# mm.net
KiCad netlist of a schematic drawn in EAGLE
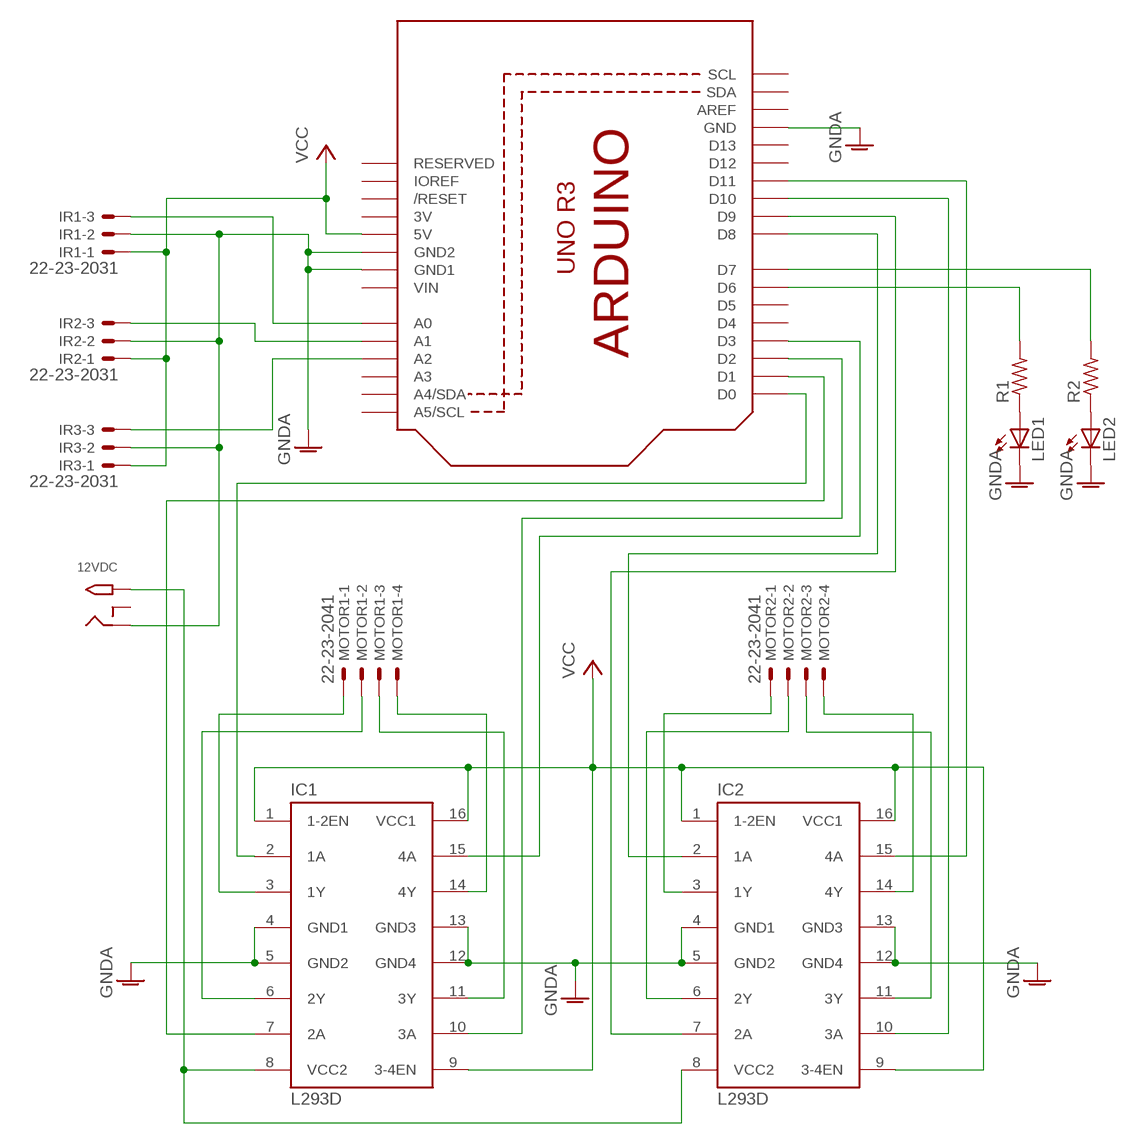
[diagram p0: schematic, sheet 1]

(export (version "E")
  (design (tool "Eeschema 10.0.6"))
  (components
    (comp (ref "12VDC")
      (value "2.1MMJACKTHM")
      (footprint "eagle-import:PJ-102A")
      (libsource (lib "eagle-import") (part "2.1MMJACKTHM"))
    )
    (comp (ref "IC1")
      (value "L293D")
      (footprint "eagle-import:DIL16")
      (libsource (lib "eagle-import") (part "L293D"))
    )
    (comp (ref "IC2")
      (value "L293D")
      (footprint "eagle-import:DIL16")
      (libsource (lib "eagle-import") (part "L293D"))
    )
    (comp (ref "IR1")
      (value "22-23-2031")
      (footprint "eagle-import:22-23-2031")
      (fields (field (name "MF") "MOLEX"))
      (libsource (lib "eagle-import") (part "22-23-2031"))
    )
    (comp (ref "IR2")
      (value "22-23-2031")
      (footprint "eagle-import:22-23-2031")
      (fields (field (name "MF") "MOLEX"))
      (libsource (lib "eagle-import") (part "22-23-2031"))
    )
    (comp (ref "IR3")
      (value "22-23-2031")
      (footprint "eagle-import:22-23-2031")
      (fields (field (name "MF") "MOLEX"))
      (libsource (lib "eagle-import") (part "22-23-2031"))
    )
    (comp (ref "LED1")
      (value "LED3MM")
      (footprint "eagle-import:LED3MM")
      (libsource (lib "eagle-import") (part "LED3MM"))
    )
    (comp (ref "LED2")
      (value "LED3MM")
      (footprint "eagle-import:LED3MM")
      (libsource (lib "eagle-import") (part "LED3MM"))
    )
    (comp (ref "MOTOR1")
      (value "22-23-2041")
      (footprint "eagle-import:22-23-2041")
      (fields (field (name "MF") "MOLEX"))
      (libsource (lib "eagle-import") (part "22-23-2041"))
    )
    (comp (ref "MOTOR2")
      (value "22-23-2041")
      (footprint "eagle-import:22-23-2041")
      (fields (field (name "MF") "MOLEX"))
      (libsource (lib "eagle-import") (part "22-23-2041"))
    )
    (comp (ref "R1")
      (value "R-US_0204/5")
      (footprint "eagle-import:0204_5")
      (libsource (lib "eagle-import") (part "R-US_0204/5"))
    )
    (comp (ref "R2")
      (value "R-US_0204/5")
      (footprint "eagle-import:0204_5")
      (libsource (lib "eagle-import") (part "R-US_0204/5"))
    )
    (comp (ref "U1")
      (value "ARDUINOR3-DIMENSION")
      (footprint "eagle-import:ARDUINOR3")
      (libsource (lib "eagle-import") (part "ARDUINOR3-DIMENSION"))
    )
  )
  (nets
    (net (code "1") (name "/3V") (class "Default")
      (node (ref "U1") (pin "3V") (pinfunction "3V_3V") (pintype "power_in"))
    )
    (net (code "2") (name "/VIN") (class "Default")
      (node (ref "U1") (pin "VIN") (pinfunction "VIN_VIN") (pintype "power_in"))
    )
    (net (code "3") (name "GNDA") (class "Default")
      (node (ref "12VDC") (pin "RING") (pinfunction "RING_RING") (pintype "bidirectional"))
      (node (ref "IC1") (pin "12") (pinfunction "GND4_12") (pintype "power_in"))
      (node (ref "IC1") (pin "13") (pinfunction "GND3_13") (pintype "power_in"))
      (node (ref "IC1") (pin "4") (pinfunction "GND1_4") (pintype "power_in"))
      (node (ref "IC1") (pin "5") (pinfunction "GND2_5") (pintype "power_in"))
      (node (ref "IC2") (pin "12") (pinfunction "GND4_12") (pintype "power_in"))
      (node (ref "IC2") (pin "13") (pinfunction "GND3_13") (pintype "power_in"))
      (node (ref "IC2") (pin "4") (pinfunction "GND1_4") (pintype "power_in"))
      (node (ref "IC2") (pin "5") (pinfunction "GND2_5") (pintype "power_in"))
      (node (ref "IR1") (pin "2") (pinfunction "S_2") (pintype "passive"))
      (node (ref "IR2") (pin "2") (pinfunction "S_2") (pintype "passive"))
      (node (ref "IR3") (pin "2") (pinfunction "S_2") (pintype "passive"))
      (node (ref "LED1") (pin "K") (pinfunction "C_K") (pintype "passive"))
      (node (ref "LED2") (pin "K") (pinfunction "C_K") (pintype "passive"))
      (node (ref "U1") (pin "GND") (pinfunction "GND_GND") (pintype "power_in"))
      (node (ref "U1") (pin "GND1") (pinfunction "GND1_GND1") (pintype "power_in"))
      (node (ref "U1") (pin "GND2") (pinfunction "GND2_GND2") (pintype "power_in"))
    )
    (net (code "4") (name "Net-(IC1-1A)") (class "Default")
      (node (ref "IC1") (pin "2") (pinfunction "1A_2") (pintype "input"))
      (node (ref "U1") (pin "D0") (pinfunction "D0_D0") (pintype "bidirectional"))
    )
    (net (code "5") (name "Net-(IC1-1Y)") (class "Default")
      (node (ref "IC1") (pin "3") (pinfunction "1Y_3") (pintype "output"))
      (node (ref "MOTOR1") (pin "1") (pinfunction "S_1") (pintype "passive"))
    )
    (net (code "6") (name "Net-(IC1-2A)") (class "Default")
      (node (ref "IC1") (pin "7") (pinfunction "2A_7") (pintype "input"))
      (node (ref "U1") (pin "D1") (pinfunction "D1_D1") (pintype "bidirectional"))
    )
    (net (code "7") (name "Net-(IC1-2Y)") (class "Default")
      (node (ref "IC1") (pin "6") (pinfunction "2Y_6") (pintype "output"))
      (node (ref "MOTOR1") (pin "2") (pinfunction "S_2") (pintype "passive"))
    )
    (net (code "8") (name "Net-(IC1-3A)") (class "Default")
      (node (ref "IC1") (pin "10") (pinfunction "3A_10") (pintype "input"))
      (node (ref "U1") (pin "D2") (pinfunction "D2_D2") (pintype "bidirectional"))
    )
    (net (code "9") (name "Net-(IC1-3Y)") (class "Default")
      (node (ref "IC1") (pin "11") (pinfunction "3Y_11") (pintype "output"))
      (node (ref "MOTOR1") (pin "3") (pinfunction "S_3") (pintype "passive"))
    )
    (net (code "10") (name "Net-(IC1-4A)") (class "Default")
      (node (ref "IC1") (pin "15") (pinfunction "4A_15") (pintype "input"))
      (node (ref "U1") (pin "D3") (pinfunction "D3_D3") (pintype "bidirectional"))
    )
    (net (code "11") (name "Net-(IC1-4Y)") (class "Default")
      (node (ref "IC1") (pin "14") (pinfunction "4Y_14") (pintype "output"))
      (node (ref "MOTOR1") (pin "4") (pinfunction "S_4") (pintype "passive"))
    )
    (net (code "12") (name "Net-(IC1-VCC2)") (class "Default")
      (node (ref "12VDC") (pin "TIP") (pinfunction "TIP_TIP") (pintype "bidirectional"))
      (node (ref "IC1") (pin "8") (pinfunction "VCC2_8") (pintype "power_in"))
      (node (ref "IC2") (pin "8") (pinfunction "VCC2_8") (pintype "power_in"))
    )
    (net (code "13") (name "Net-(IC2-1A)") (class "Default")
      (node (ref "IC2") (pin "2") (pinfunction "1A_2") (pintype "input"))
      (node (ref "U1") (pin "D8") (pinfunction "D8_D8") (pintype "bidirectional"))
    )
    (net (code "14") (name "Net-(IC2-1Y)") (class "Default")
      (node (ref "IC2") (pin "3") (pinfunction "1Y_3") (pintype "output"))
      (node (ref "MOTOR2") (pin "1") (pinfunction "S_1") (pintype "passive"))
    )
    (net (code "15") (name "Net-(IC2-2A)") (class "Default")
      (node (ref "IC2") (pin "7") (pinfunction "2A_7") (pintype "input"))
      (node (ref "U1") (pin "D9") (pinfunction "D9_D9") (pintype "bidirectional"))
    )
    (net (code "16") (name "Net-(IC2-2Y)") (class "Default")
      (node (ref "IC2") (pin "6") (pinfunction "2Y_6") (pintype "output"))
      (node (ref "MOTOR2") (pin "2") (pinfunction "S_2") (pintype "passive"))
    )
    (net (code "17") (name "Net-(IC2-3A)") (class "Default")
      (node (ref "IC2") (pin "10") (pinfunction "3A_10") (pintype "input"))
      (node (ref "U1") (pin "D10") (pinfunction "D10_D10") (pintype "bidirectional"))
    )
    (net (code "18") (name "Net-(IC2-3Y)") (class "Default")
      (node (ref "IC2") (pin "11") (pinfunction "3Y_11") (pintype "output"))
      (node (ref "MOTOR2") (pin "3") (pinfunction "S_3") (pintype "passive"))
    )
    (net (code "19") (name "Net-(IC2-4A)") (class "Default")
      (node (ref "IC2") (pin "15") (pinfunction "4A_15") (pintype "input"))
      (node (ref "U1") (pin "D11") (pinfunction "D11_D11") (pintype "bidirectional"))
    )
    (net (code "20") (name "Net-(IC2-4Y)") (class "Default")
      (node (ref "IC2") (pin "14") (pinfunction "4Y_14") (pintype "output"))
      (node (ref "MOTOR2") (pin "4") (pinfunction "S_4") (pintype "passive"))
    )
    (net (code "21") (name "Net-(IR1C-S)") (class "Default")
      (node (ref "IR1") (pin "3") (pinfunction "S_3") (pintype "passive"))
      (node (ref "U1") (pin "A0") (pinfunction "A0_A0") (pintype "bidirectional"))
    )
    (net (code "22") (name "Net-(IR2C-S)") (class "Default")
      (node (ref "IR2") (pin "3") (pinfunction "S_3") (pintype "passive"))
      (node (ref "U1") (pin "A1") (pinfunction "A1_A1") (pintype "bidirectional"))
    )
    (net (code "23") (name "Net-(IR3C-S)") (class "Default")
      (node (ref "IR3") (pin "3") (pinfunction "S_3") (pintype "passive"))
      (node (ref "U1") (pin "A2") (pinfunction "A2_A2") (pintype "bidirectional"))
    )
    (net (code "24") (name "Net-(LED1-PadA)") (class "Default")
      (node (ref "LED1") (pin "A") (pinfunction "A_A") (pintype "passive"))
      (node (ref "R1") (pin "1") (pinfunction "1_1") (pintype "passive"))
    )
    (net (code "25") (name "Net-(LED2-PadA)") (class "Default")
      (node (ref "LED2") (pin "A") (pinfunction "A_A") (pintype "passive"))
      (node (ref "R2") (pin "1") (pinfunction "1_1") (pintype "passive"))
    )
    (net (code "26") (name "Net-(R1-Pad2)") (class "Default")
      (node (ref "R1") (pin "2") (pinfunction "2_2") (pintype "passive"))
      (node (ref "U1") (pin "D6") (pinfunction "D6_D6") (pintype "bidirectional"))
    )
    (net (code "27") (name "Net-(R2-Pad2)") (class "Default")
      (node (ref "R2") (pin "2") (pinfunction "2_2") (pintype "passive"))
      (node (ref "U1") (pin "D7") (pinfunction "D7_D7") (pintype "bidirectional"))
    )
    (net (code "28") (name "VCC") (class "Default")
      (node (ref "IC1") (pin "1") (pinfunction "1-2EN_1") (pintype "input"))
      (node (ref "IC1") (pin "16") (pinfunction "VCC1_16") (pintype "power_in"))
      (node (ref "IC1") (pin "9") (pinfunction "3-4EN_9") (pintype "input"))
      (node (ref "IC2") (pin "1") (pinfunction "1-2EN_1") (pintype "input"))
      (node (ref "IC2") (pin "16") (pinfunction "VCC1_16") (pintype "power_in"))
      (node (ref "IC2") (pin "9") (pinfunction "3-4EN_9") (pintype "input"))
      (node (ref "IR1") (pin "1") (pinfunction "S_1") (pintype "passive"))
      (node (ref "IR2") (pin "1") (pinfunction "S_1") (pintype "passive"))
      (node (ref "IR3") (pin "1") (pinfunction "S_1") (pintype "passive"))
      (node (ref "U1") (pin "5V") (pinfunction "5V_5V") (pintype "power_in"))
    )
    (net (code "29") (name "unconnected-(12VDC-PadRING_SW)") (class "Default")
      (node (ref "12VDC") (pin "RING_SW") (pinfunction "RING_SW_RING_SW") (pintype "bidirectional"))
    )
    (net (code "30") (name "unconnected-(U1-A4{slash}SDA-PadA4)") (class "Default")
      (node (ref "U1") (pin "A4") (pinfunction "A4/SDA_A4") (pintype "bidirectional"))
    )
    (net (code "31") (name "unconnected-(U1-A5{slash}SCL-PadA5)") (class "Default")
      (node (ref "U1") (pin "A5") (pinfunction "A5/SCL_A5") (pintype "bidirectional"))
    )
    (net (code "32") (name "unconnected-(U1-PadA3)") (class "Default")
      (node (ref "U1") (pin "A3") (pinfunction "A3_A3") (pintype "bidirectional"))
    )
    (net (code "33") (name "unconnected-(U1-PadAREF)") (class "Default")
      (node (ref "U1") (pin "AREF") (pinfunction "AREF_AREF") (pintype "bidirectional"))
    )
    (net (code "34") (name "unconnected-(U1-PadD4)") (class "Default")
      (node (ref "U1") (pin "D4") (pinfunction "D4_D4") (pintype "bidirectional"))
    )
    (net (code "35") (name "unconnected-(U1-PadD5)") (class "Default")
      (node (ref "U1") (pin "D5") (pinfunction "D5_D5") (pintype "bidirectional"))
    )
    (net (code "36") (name "unconnected-(U1-PadD12)") (class "Default")
      (node (ref "U1") (pin "D12") (pinfunction "D12_D12") (pintype "bidirectional"))
    )
    (net (code "37") (name "unconnected-(U1-PadD13)") (class "Default")
      (node (ref "U1") (pin "D13") (pinfunction "D13_D13") (pintype "bidirectional"))
    )
    (net (code "38") (name "unconnected-(U1-PadIOREF)") (class "Default")
      (node (ref "U1") (pin "IOREF") (pinfunction "IOREF_IOREF") (pintype "output"))
    )
    (net (code "39") (name "unconnected-(U1-PadRESERVED)") (class "Default")
      (node (ref "U1") (pin "RESERVED") (pinfunction "RESERVED_RESERVED") (pintype "no_connect"))
    )
    (net (code "40") (name "unconnected-(U1-PadSCL)") (class "Default")
      (node (ref "U1") (pin "SCL") (pinfunction "SCL_SCL") (pintype "bidirectional"))
    )
    (net (code "41") (name "unconnected-(U1-PadSDA)") (class "Default")
      (node (ref "U1") (pin "SDA") (pinfunction "SDA_SDA") (pintype "bidirectional"))
    )
    (net (code "42") (name "unconnected-(U1-{slash}RESET-PadRESET)") (class "Default")
      (node (ref "U1") (pin "RESET") (pinfunction "/RESET_RESET") (pintype "bidirectional"))
    )
  )
)
